# CoffretClimatiquePCBV3.net
KiCad netlist of a schematic drawn in EAGLE
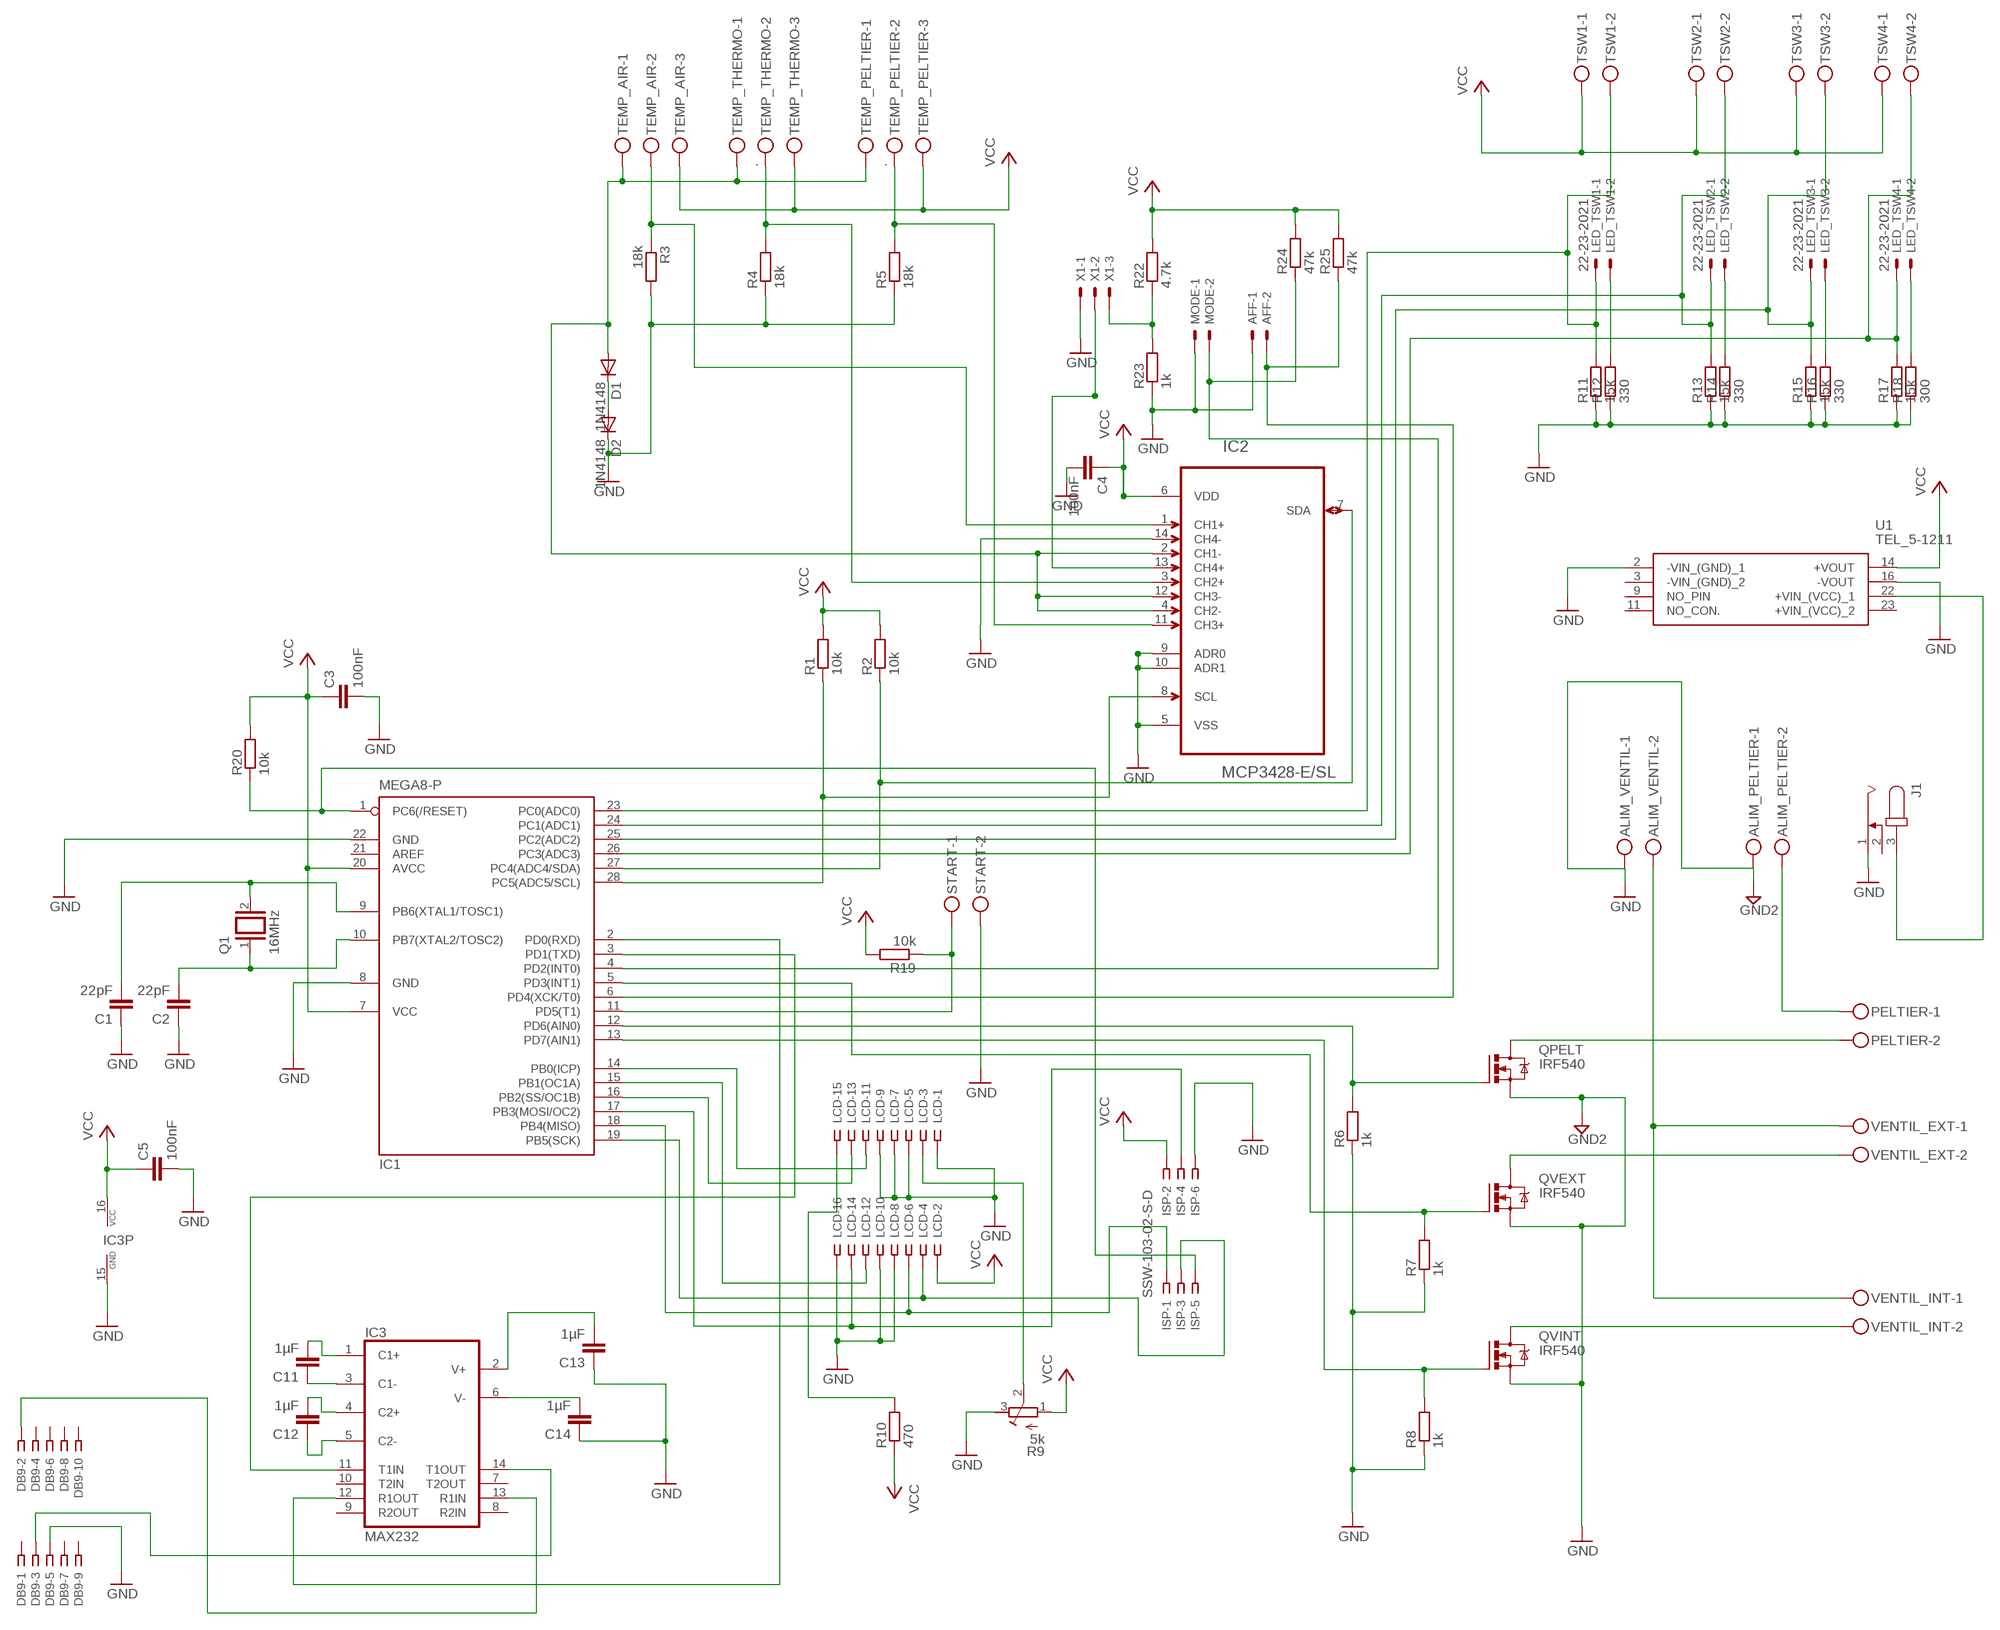
[diagram p0: schematic, sheet 1]

(export (version "E")
  (design (tool "Eeschema 10.0.6"))
  (components
    (comp (ref "AFF")
      (value "22-23-2021")
      (footprint "eagle-import:22-23-2021")
      (fields (field (name "MF") "MOLEX"))
      (libsource (lib "eagle-import") (part "22-23-2021"))
    )
    (comp (ref "ALIM_PELTIER")
      (value "MKDSN1,5/2-5,08")
      (footprint "eagle-import:MKDSN1,5_2-5,08")
      (fields (field (name "MPN") "MKDSN 1,5/2-5.08"))
      (libsource (lib "eagle-import") (part "MKDSN1,5/2-5,08"))
    )
    (comp (ref "ALIM_VENTIL")
      (value "MKDSN1,5/2-5,08")
      (footprint "eagle-import:MKDSN1,5_2-5,08")
      (fields (field (name "MPN") "MKDSN 1,5/2-5.08"))
      (libsource (lib "eagle-import") (part "MKDSN1,5/2-5,08"))
    )
    (comp (ref "C1")
      (value "22pF")
      (footprint "eagle-import:C075-032X103")
      (libsource (lib "eagle-import") (part "C-EU075-032X103"))
    )
    (comp (ref "C2")
      (value "22pF")
      (footprint "eagle-import:C075-032X103")
      (libsource (lib "eagle-import") (part "C-EU075-032X103"))
    )
    (comp (ref "C3")
      (value "100nF")
      (footprint "eagle-import:C1206")
      (libsource (lib "eagle-import") (part "C-EUC1206"))
    )
    (comp (ref "C4")
      (value "100nF")
      (footprint "eagle-import:C1206")
      (libsource (lib "eagle-import") (part "C-EUC1206"))
    )
    (comp (ref "C5")
      (value "100nF")
      (footprint "eagle-import:C1206")
      (libsource (lib "eagle-import") (part "C-EUC1206"))
    )
    (comp (ref "C11")
      (value "1µF")
      (footprint "eagle-import:C1206")
      (libsource (lib "eagle-import") (part "C-EUC1206"))
    )
    (comp (ref "C12")
      (value "1µF")
      (footprint "eagle-import:C1206")
      (libsource (lib "eagle-import") (part "C-EUC1206"))
    )
    (comp (ref "C13")
      (value "1µF")
      (footprint "eagle-import:C1206")
      (libsource (lib "eagle-import") (part "C-EUC1206"))
    )
    (comp (ref "C14")
      (value "1µF")
      (footprint "eagle-import:C1206")
      (libsource (lib "eagle-import") (part "C-EUC1206"))
    )
    (comp (ref "D1")
      (value "1N4148")
      (footprint "eagle-import:DO35-10")
      (libsource (lib "eagle-import") (part "1N4148DO35-10"))
    )
    (comp (ref "D2")
      (value "1N4148")
      (footprint "eagle-import:DO35-10")
      (libsource (lib "eagle-import") (part "1N4148DO35-10"))
    )
    (comp (ref "DB9")
      (value "SSW-105-02-S-D")
      (footprint "eagle-import:SSW-105-02-S-D")
      (libsource (lib "eagle-import") (part "SSW-105-02-S-D"))
    )
    (comp (ref "IC1")
      (value "MEGA8-P")
      (footprint "eagle-import:DIL28-3")
      (libsource (lib "eagle-import") (part "MEGA8-P"))
    )
    (comp (ref "IC2")
      (value "MCP3428-E/SL")
      (footprint "eagle-import:SOIC127P600X175-14N")
      (libsource (lib "eagle-import") (part "MCP3428-E/SL"))
    )
    (comp (ref "IC3")
      (value "MAX232")
      (footprint "eagle-import:DIL16")
      (fields (field (name "MF") "MAXIM") (field (name "MPN") "MAX232ACPE+"))
      (libsource (lib "eagle-import") (part "MAX232"))
    )
    (comp (ref "ISP")
      (value "SSW-103-02-S-D")
      (footprint "eagle-import:SSW-103-02-S-D")
      (libsource (lib "eagle-import") (part "SSW-103-02-S-D"))
    )
    (comp (ref "J1")
      (value "JACK-PLUG1")
      (footprint "eagle-import:SPC4078")
      (libsource (lib "eagle-import") (part "JACK-PLUG1"))
    )
    (comp (ref "LCD")
      (value "SSW-108-02-S-D")
      (footprint "eagle-import:SSW-108-02-S-D")
      (libsource (lib "eagle-import") (part "SSW-108-02-S-D"))
    )
    (comp (ref "LED_TSW1")
      (value "22-23-2021")
      (footprint "eagle-import:22-23-2021")
      (fields (field (name "MF") "MOLEX"))
      (libsource (lib "eagle-import") (part "22-23-2021"))
    )
    (comp (ref "LED_TSW2")
      (value "22-23-2021")
      (footprint "eagle-import:22-23-2021")
      (fields (field (name "MF") "MOLEX"))
      (libsource (lib "eagle-import") (part "22-23-2021"))
    )
    (comp (ref "LED_TSW3")
      (value "22-23-2021")
      (footprint "eagle-import:22-23-2021")
      (fields (field (name "MF") "MOLEX"))
      (libsource (lib "eagle-import") (part "22-23-2021"))
    )
    (comp (ref "LED_TSW4")
      (value "22-23-2021")
      (footprint "eagle-import:22-23-2021")
      (fields (field (name "MF") "MOLEX"))
      (libsource (lib "eagle-import") (part "22-23-2021"))
    )
    (comp (ref "MODE")
      (value "22-23-2021")
      (footprint "eagle-import:22-23-2021")
      (fields (field (name "MF") "MOLEX"))
      (libsource (lib "eagle-import") (part "22-23-2021"))
    )
    (comp (ref "PELTIER")
      (value "MKDSN1,5/2-5,08")
      (footprint "eagle-import:MKDSN1,5_2-5,08")
      (fields (field (name "MPN") "MKDSN 1,5/2-5.08"))
      (libsource (lib "eagle-import") (part "MKDSN1,5/2-5,08"))
    )
    (comp (ref "Q1")
      (value "16MHz")
      (footprint "eagle-import:QS")
      (libsource (lib "eagle-import") (part "XTAL/S"))
    )
    (comp (ref "QPELT")
      (value "IRF540")
      (footprint "eagle-import:TO220BV")
      (libsource (lib "eagle-import") (part "IRF540"))
    )
    (comp (ref "QVEXT")
      (value "IRF540")
      (footprint "eagle-import:TO220BV")
      (libsource (lib "eagle-import") (part "IRF540"))
    )
    (comp (ref "QVINT")
      (value "IRF540")
      (footprint "eagle-import:TO220BV")
      (libsource (lib "eagle-import") (part "IRF540"))
    )
    (comp (ref "R1")
      (value "10k")
      (footprint "eagle-import:R0805")
      (libsource (lib "eagle-import") (part "R-EU_R0805"))
    )
    (comp (ref "R2")
      (value "10k")
      (footprint "eagle-import:R0805")
      (libsource (lib "eagle-import") (part "R-EU_R0805"))
    )
    (comp (ref "R3")
      (value "18k")
      (footprint "eagle-import:0207_10")
      (libsource (lib "eagle-import") (part "R-EU_0207/10"))
    )
    (comp (ref "R4")
      (value "18k")
      (footprint "eagle-import:0207_10")
      (libsource (lib "eagle-import") (part "R-EU_0207/10"))
    )
    (comp (ref "R5")
      (value "18k")
      (footprint "eagle-import:0207_10")
      (libsource (lib "eagle-import") (part "R-EU_0207/10"))
    )
    (comp (ref "R6")
      (value "1k")
      (footprint "eagle-import:0207_10")
      (libsource (lib "eagle-import") (part "R-EU_0207/10"))
    )
    (comp (ref "R7")
      (value "1k")
      (footprint "eagle-import:0207_10")
      (libsource (lib "eagle-import") (part "R-EU_0207/10"))
    )
    (comp (ref "R8")
      (value "1k")
      (footprint "eagle-import:0207_10")
      (libsource (lib "eagle-import") (part "R-EU_0207/10"))
    )
    (comp (ref "R9")
      (value "5k")
      (footprint "eagle-import:RTRIM64P")
      (libsource (lib "eagle-import") (part "R-TRIMM64P"))
    )
    (comp (ref "R10")
      (value "470")
      (footprint "eagle-import:0207_10")
      (libsource (lib "eagle-import") (part "R-EU_0207/10"))
    )
    (comp (ref "R11")
      (value "15k")
      (footprint "eagle-import:0207_10")
      (libsource (lib "eagle-import") (part "R-EU_0207/10"))
    )
    (comp (ref "R12")
      (value "330")
      (footprint "eagle-import:0207_10")
      (libsource (lib "eagle-import") (part "R-EU_0207/10"))
    )
    (comp (ref "R13")
      (value "15k")
      (footprint "eagle-import:0207_10")
      (libsource (lib "eagle-import") (part "R-EU_0207/10"))
    )
    (comp (ref "R14")
      (value "330")
      (footprint "eagle-import:0207_10")
      (libsource (lib "eagle-import") (part "R-EU_0207/10"))
    )
    (comp (ref "R15")
      (value "15k")
      (footprint "eagle-import:0207_10")
      (libsource (lib "eagle-import") (part "R-EU_0207/10"))
    )
    (comp (ref "R16")
      (value "330")
      (footprint "eagle-import:0207_10")
      (libsource (lib "eagle-import") (part "R-EU_0207/10"))
    )
    (comp (ref "R17")
      (value "15k")
      (footprint "eagle-import:0207_10")
      (libsource (lib "eagle-import") (part "R-EU_0207/10"))
    )
    (comp (ref "R18")
      (value "300")
      (footprint "eagle-import:0207_10")
      (libsource (lib "eagle-import") (part "R-EU_0207/10"))
    )
    (comp (ref "R19")
      (value "10k")
      (footprint "eagle-import:0207_10")
      (libsource (lib "eagle-import") (part "R-EU_0207/10"))
    )
    (comp (ref "R20")
      (value "10k")
      (footprint "eagle-import:0207_10")
      (libsource (lib "eagle-import") (part "R-EU_0207/10"))
    )
    (comp (ref "R22")
      (value "4.7k")
      (footprint "eagle-import:0207_10")
      (libsource (lib "eagle-import") (part "R-EU_0207/10"))
    )
    (comp (ref "R23")
      (value "1k")
      (footprint "eagle-import:0207_10")
      (libsource (lib "eagle-import") (part "R-EU_0207/10"))
    )
    (comp (ref "R24")
      (value "47k")
      (footprint "eagle-import:0207_10")
      (libsource (lib "eagle-import") (part "R-EU_0207/10"))
    )
    (comp (ref "R25")
      (value "47k")
      (footprint "eagle-import:0207_10")
      (libsource (lib "eagle-import") (part "R-EU_0207/10"))
    )
    (comp (ref "START")
      (value "MKDSN1,5/2-5,08")
      (footprint "eagle-import:MKDSN1,5_2-5,08")
      (fields (field (name "MPN") "MKDSN 1,5/2-5.08"))
      (libsource (lib "eagle-import") (part "MKDSN1,5/2-5,08"))
    )
    (comp (ref "TEMP_AIR")
      (value "MKDSN1,5/3-5,08")
      (footprint "eagle-import:MKDSN1,5_3-5,08")
      (fields (field (name "MPN") "SMKDSN1,5/3-5,08"))
      (libsource (lib "eagle-import") (part "MKDSN1,5/3-5,08"))
    )
    (comp (ref "TEMP_PELTIER")
      (value ".")
      (footprint "eagle-import:MKDSN1,5_3-5,08")
      (fields (field (name "MPN") "SMKDSN1,5/3-5,08"))
      (libsource (lib "eagle-import") (part "MKDSN1,5/3-5,08"))
    )
    (comp (ref "TEMP_THERMO")
      (value ".")
      (footprint "eagle-import:MKDSN1,5_3-5,08")
      (fields (field (name "MPN") "SMKDSN1,5/3-5,08"))
      (libsource (lib "eagle-import") (part "MKDSN1,5/3-5,08"))
    )
    (comp (ref "TSW1")
      (value "MKDSN1,5/2-5,08")
      (footprint "eagle-import:MKDSN1,5_2-5,08")
      (fields (field (name "MPN") "MKDSN 1,5/2-5.08"))
      (libsource (lib "eagle-import") (part "MKDSN1,5/2-5,08"))
    )
    (comp (ref "TSW2")
      (value "MKDSN1,5/2-5,08")
      (footprint "eagle-import:MKDSN1,5_2-5,08")
      (fields (field (name "MPN") "MKDSN 1,5/2-5.08"))
      (libsource (lib "eagle-import") (part "MKDSN1,5/2-5,08"))
    )
    (comp (ref "TSW3")
      (value "MKDSN1,5/2-5,08")
      (footprint "eagle-import:MKDSN1,5_2-5,08")
      (fields (field (name "MPN") "MKDSN 1,5/2-5.08"))
      (libsource (lib "eagle-import") (part "MKDSN1,5/2-5,08"))
    )
    (comp (ref "TSW4")
      (value "MKDSN1,5/2-5,08")
      (footprint "eagle-import:MKDSN1,5_2-5,08")
      (fields (field (name "MPN") "MKDSN 1,5/2-5.08"))
      (libsource (lib "eagle-import") (part "MKDSN1,5/2-5,08"))
    )
    (comp (ref "U1")
      (value "TEL_5-1211")
      (footprint "eagle-import:TEL-5-1211")
      (fields
        (field (name "MANUFACTURER_PART_NUMBER") "TEL 5-1211")
        (field (name "MOUSER_PART_NUMBER") "495-TEL-5-1211")
        (field (name "RS_PART_NUMBER") "4667051")
      )
      (libsource (lib "eagle-import") (part "TEL_5-1211"))
    )
    (comp (ref "VENTIL_EXT")
      (value "MKDSN1,5/2-5,08")
      (footprint "eagle-import:MKDSN1,5_2-5,08")
      (fields (field (name "MPN") "MKDSN 1,5/2-5.08"))
      (libsource (lib "eagle-import") (part "MKDSN1,5/2-5,08"))
    )
    (comp (ref "VENTIL_INT")
      (value "MKDSN1,5/2-5,08")
      (footprint "eagle-import:MKDSN1,5_2-5,08")
      (fields (field (name "MPN") "MKDSN 1,5/2-5.08"))
      (libsource (lib "eagle-import") (part "MKDSN1,5/2-5,08"))
    )
    (comp (ref "X1")
      (value "22-23-2031")
      (footprint "eagle-import:22-23-2031")
      (fields (field (name "MF") "MOLEX"))
      (libsource (lib "eagle-import") (part "22-23-2031"))
    )
  )
  (nets
    (net (code "1") (name "GND") (class "Default")
      (node (ref "AFF") (pin "1") (pinfunction "S_1") (pintype "passive"))
      (node (ref "ALIM_PELTIER") (pin "1") (pinfunction "KL_1") (pintype "passive"))
      (node (ref "ALIM_VENTIL") (pin "1") (pinfunction "KL_1") (pintype "passive"))
      (node (ref "C1") (pin "1") (pinfunction "1_1") (pintype "passive"))
      (node (ref "C13") (pin "1") (pinfunction "1_1") (pintype "passive"))
      (node (ref "C14") (pin "1") (pinfunction "1_1") (pintype "passive"))
      (node (ref "C2") (pin "1") (pinfunction "1_1") (pintype "passive"))
      (node (ref "C3") (pin "2") (pinfunction "2_2") (pintype "passive"))
      (node (ref "C4") (pin "2") (pinfunction "2_2") (pintype "passive"))
      (node (ref "C5") (pin "2") (pinfunction "2_2") (pintype "passive"))
      (node (ref "D2") (pin "C") (pinfunction "C_C") (pintype "passive"))
      (node (ref "DB9") (pin "5") (pinfunction "1_5") (pintype "passive"))
      (node (ref "IC1") (pin "22") (pinfunction "GND_22") (pintype "power_in"))
      (node (ref "IC1") (pin "8") (pinfunction "GND_8") (pintype "power_in"))
      (node (ref "IC2") (pin "10") (pinfunction "ADR1_10") (pintype "passive"))
      (node (ref "IC2") (pin "14") (pinfunction "CH4-_14") (pintype "input"))
      (node (ref "IC2") (pin "5") (pinfunction "VSS_5") (pintype "power_in"))
      (node (ref "IC2") (pin "9") (pinfunction "ADR0_9") (pintype "passive"))
      (node (ref "IC3") (pin "15") (pinfunction "GND_15") (pintype "power_in"))
      (node (ref "ISP") (pin "6") (pinfunction "1_6") (pintype "passive"))
      (node (ref "J1") (pin "1") (pinfunction "1_1") (pintype "passive"))
      (node (ref "LCD") (pin "1") (pinfunction "1_1") (pintype "passive"))
      (node (ref "LCD") (pin "10") (pinfunction "1_10") (pintype "passive"))
      (node (ref "LCD") (pin "16") (pinfunction "1_16") (pintype "passive"))
      (node (ref "LCD") (pin "5") (pinfunction "1_5") (pintype "passive"))
      (node (ref "LCD") (pin "7") (pinfunction "1_7") (pintype "passive"))
      (node (ref "LCD") (pin "8") (pinfunction "1_8") (pintype "passive"))
      (node (ref "LCD") (pin "9") (pinfunction "1_9") (pintype "passive"))
      (node (ref "MODE") (pin "1") (pinfunction "S_1") (pintype "passive"))
      (node (ref "QPELT") (pin "S") (pinfunction "S_S") (pintype "passive"))
      (node (ref "QVEXT") (pin "S") (pinfunction "S_S") (pintype "passive"))
      (node (ref "QVINT") (pin "S") (pinfunction "S_S") (pintype "passive"))
      (node (ref "R11") (pin "1") (pinfunction "1_1") (pintype "passive"))
      (node (ref "R12") (pin "1") (pinfunction "1_1") (pintype "passive"))
      (node (ref "R13") (pin "1") (pinfunction "1_1") (pintype "passive"))
      (node (ref "R14") (pin "1") (pinfunction "1_1") (pintype "passive"))
      (node (ref "R15") (pin "1") (pinfunction "1_1") (pintype "passive"))
      (node (ref "R16") (pin "1") (pinfunction "1_1") (pintype "passive"))
      (node (ref "R17") (pin "1") (pinfunction "1_1") (pintype "passive"))
      (node (ref "R18") (pin "1") (pinfunction "1_1") (pintype "passive"))
      (node (ref "R23") (pin "1") (pinfunction "1_1") (pintype "passive"))
      (node (ref "R3") (pin "2") (pinfunction "2_2") (pintype "passive"))
      (node (ref "R4") (pin "1") (pinfunction "1_1") (pintype "passive"))
      (node (ref "R5") (pin "1") (pinfunction "1_1") (pintype "passive"))
      (node (ref "R6") (pin "1") (pinfunction "1_1") (pintype "passive"))
      (node (ref "R7") (pin "1") (pinfunction "1_1") (pintype "passive"))
      (node (ref "R8") (pin "1") (pinfunction "1_1") (pintype "passive"))
      (node (ref "R9") (pin "3") (pinfunction "E_3") (pintype "passive"))
      (node (ref "START") (pin "2") (pinfunction "KL_2") (pintype "passive"))
      (node (ref "U1") (pin "16") (pinfunction "-VOUT_16") (pintype "bidirectional"))
      (node (ref "U1") (pin "2") (pinfunction "-VIN_(GND)_1_2") (pintype "bidirectional"))
      (node (ref "X1") (pin "1") (pinfunction "S_1") (pintype "passive"))
    )
    (net (code "2") (name "Net-(AFFB-S)") (class "Default")
      (node (ref "AFF") (pin "2") (pinfunction "S_2") (pintype "passive"))
      (node (ref "IC1") (pin "6") (pinfunction "PD4(XCK/T0)_6") (pintype "bidirectional"))
      (node (ref "R25") (pin "1") (pinfunction "1_1") (pintype "passive"))
    )
    (net (code "3") (name "Net-(ALIM_PELTIERB-KL)") (class "Default")
      (node (ref "ALIM_PELTIER") (pin "2") (pinfunction "KL_2") (pintype "passive"))
      (node (ref "PELTIER") (pin "1") (pinfunction "KL_1") (pintype "passive"))
    )
    (net (code "4") (name "Net-(ALIM_VENTILB-KL)") (class "Default")
      (node (ref "ALIM_VENTIL") (pin "2") (pinfunction "KL_2") (pintype "passive"))
      (node (ref "VENTIL_EXT") (pin "1") (pinfunction "KL_1") (pintype "passive"))
      (node (ref "VENTIL_INT") (pin "1") (pinfunction "KL_1") (pintype "passive"))
    )
    (net (code "5") (name "Net-(D1-PadC)") (class "Default")
      (node (ref "D1") (pin "C") (pinfunction "C_C") (pintype "passive"))
      (node (ref "D2") (pin "A") (pinfunction "A_A") (pintype "passive"))
    )
    (net (code "6") (name "Net-(DB9C-1)") (class "Default")
      (node (ref "DB9") (pin "2") (pinfunction "1_2") (pintype "passive"))
      (node (ref "IC3") (pin "13") (pinfunction "R1IN_13") (pintype "input"))
    )
    (net (code "7") (name "Net-(DB9D-1)") (class "Default")
      (node (ref "DB9") (pin "3") (pinfunction "1_3") (pintype "passive"))
      (node (ref "IC3") (pin "14") (pinfunction "T1OUT_14") (pintype "output"))
    )
    (net (code "8") (name "Net-(IC1-PB0(ICP))") (class "Default")
      (node (ref "IC1") (pin "14") (pinfunction "PB0(ICP)_14") (pintype "bidirectional"))
      (node (ref "LCD") (pin "11") (pinfunction "1_11") (pintype "passive"))
    )
    (net (code "9") (name "Net-(IC1-PB1(OC1A))") (class "Default")
      (node (ref "IC1") (pin "15") (pinfunction "PB1(OC1A)_15") (pintype "bidirectional"))
      (node (ref "LCD") (pin "12") (pinfunction "1_12") (pintype "passive"))
    )
    (net (code "10") (name "Net-(IC1-PB2(SS{slash}OC1B))") (class "Default")
      (node (ref "IC1") (pin "16") (pinfunction "PB2(SS/OC1B)_16") (pintype "bidirectional"))
      (node (ref "LCD") (pin "13") (pinfunction "1_13") (pintype "passive"))
    )
    (net (code "11") (name "Net-(IC1-PB3(MOSI{slash}OC2))") (class "Default")
      (node (ref "IC1") (pin "17") (pinfunction "PB3(MOSI/OC2)_17") (pintype "bidirectional"))
      (node (ref "ISP") (pin "4") (pinfunction "1_4") (pintype "passive"))
      (node (ref "LCD") (pin "14") (pinfunction "1_14") (pintype "passive"))
    )
    (net (code "12") (name "Net-(IC1-PB4(MISO))") (class "Default")
      (node (ref "IC1") (pin "18") (pinfunction "PB4(MISO)_18") (pintype "bidirectional"))
      (node (ref "ISP") (pin "1") (pinfunction "1_1") (pintype "passive"))
      (node (ref "LCD") (pin "6") (pinfunction "1_6") (pintype "passive"))
    )
    (net (code "13") (name "Net-(IC1-PB5(SCK))") (class "Default")
      (node (ref "IC1") (pin "19") (pinfunction "PB5(SCK)_19") (pintype "bidirectional"))
      (node (ref "ISP") (pin "3") (pinfunction "1_3") (pintype "passive"))
      (node (ref "LCD") (pin "4") (pinfunction "1_4") (pintype "passive"))
    )
    (net (code "14") (name "Net-(IC1-PB6(XTAL1{slash}TOSC1))") (class "Default")
      (node (ref "C1") (pin "2") (pinfunction "2_2") (pintype "passive"))
      (node (ref "IC1") (pin "9") (pinfunction "PB6(XTAL1/TOSC1)_9") (pintype "bidirectional"))
      (node (ref "Q1") (pin "2") (pinfunction "2_2") (pintype "passive"))
    )
    (net (code "15") (name "Net-(IC1-PB7(XTAL2{slash}TOSC2))") (class "Default")
      (node (ref "C2") (pin "2") (pinfunction "2_2") (pintype "passive"))
      (node (ref "IC1") (pin "10") (pinfunction "PB7(XTAL2/TOSC2)_10") (pintype "bidirectional"))
      (node (ref "Q1") (pin "1") (pinfunction "1_1") (pintype "passive"))
    )
    (net (code "16") (name "Net-(IC1-PC0(ADC0))") (class "Default")
      (node (ref "IC1") (pin "23") (pinfunction "PC0(ADC0)_23") (pintype "bidirectional"))
      (node (ref "LED_TSW1") (pin "1") (pinfunction "S_1") (pintype "passive"))
      (node (ref "R11") (pin "2") (pinfunction "2_2") (pintype "passive"))
      (node (ref "TSW1") (pin "2") (pinfunction "KL_2") (pintype "passive"))
    )
    (net (code "17") (name "Net-(IC1-PC1(ADC1))") (class "Default")
      (node (ref "IC1") (pin "24") (pinfunction "PC1(ADC1)_24") (pintype "bidirectional"))
      (node (ref "LED_TSW2") (pin "1") (pinfunction "S_1") (pintype "passive"))
      (node (ref "R13") (pin "2") (pinfunction "2_2") (pintype "passive"))
      (node (ref "TSW2") (pin "2") (pinfunction "KL_2") (pintype "passive"))
    )
    (net (code "18") (name "Net-(IC1-PC2(ADC2))") (class "Default")
      (node (ref "IC1") (pin "25") (pinfunction "PC2(ADC2)_25") (pintype "bidirectional"))
      (node (ref "LED_TSW3") (pin "1") (pinfunction "S_1") (pintype "passive"))
      (node (ref "R15") (pin "2") (pinfunction "2_2") (pintype "passive"))
      (node (ref "TSW3") (pin "2") (pinfunction "KL_2") (pintype "passive"))
    )
    (net (code "19") (name "Net-(IC1-PC3(ADC3))") (class "Default")
      (node (ref "IC1") (pin "26") (pinfunction "PC3(ADC3)_26") (pintype "bidirectional"))
      (node (ref "LED_TSW4") (pin "1") (pinfunction "S_1") (pintype "passive"))
      (node (ref "R17") (pin "2") (pinfunction "2_2") (pintype "passive"))
      (node (ref "TSW4") (pin "2") (pinfunction "KL_2") (pintype "passive"))
    )
    (net (code "20") (name "Net-(IC1-PC4(ADC4{slash}SDA))") (class "Default")
      (node (ref "IC1") (pin "27") (pinfunction "PC4(ADC4/SDA)_27") (pintype "bidirectional"))
      (node (ref "IC2") (pin "7") (pinfunction "SDA_7") (pintype "bidirectional"))
      (node (ref "R2") (pin "1") (pinfunction "1_1") (pintype "passive"))
    )
    (net (code "21") (name "Net-(IC1-PC5(ADC5{slash}SCL))") (class "Default")
      (node (ref "IC1") (pin "28") (pinfunction "PC5(ADC5/SCL)_28") (pintype "bidirectional"))
      (node (ref "IC2") (pin "8") (pinfunction "SCL_8") (pintype "input"))
      (node (ref "R1") (pin "1") (pinfunction "1_1") (pintype "passive"))
    )
    (net (code "22") (name "Net-(IC1-PC6({slash}RESET))") (class "Default")
      (node (ref "IC1") (pin "1") (pinfunction "PC6(/RESET)_1") (pintype "bidirectional"))
      (node (ref "ISP") (pin "5") (pinfunction "1_5") (pintype "passive"))
      (node (ref "R20") (pin "1") (pinfunction "1_1") (pintype "passive"))
    )
    (net (code "23") (name "Net-(IC1-PD0(RXD))") (class "Default")
      (node (ref "IC1") (pin "2") (pinfunction "PD0(RXD)_2") (pintype "bidirectional"))
      (node (ref "IC3") (pin "12") (pinfunction "R1OUT_12") (pintype "output"))
    )
    (net (code "24") (name "Net-(IC1-PD1(TXD))") (class "Default")
      (node (ref "IC1") (pin "3") (pinfunction "PD1(TXD)_3") (pintype "bidirectional"))
      (node (ref "IC3") (pin "11") (pinfunction "T1IN_11") (pintype "input"))
    )
    (net (code "25") (name "Net-(IC1-PD2(INT0))") (class "Default")
      (node (ref "IC1") (pin "4") (pinfunction "PD2(INT0)_4") (pintype "bidirectional"))
      (node (ref "MODE") (pin "2") (pinfunction "S_2") (pintype "passive"))
      (node (ref "R24") (pin "1") (pinfunction "1_1") (pintype "passive"))
    )
    (net (code "26") (name "Net-(IC1-PD3(INT1))") (class "Default")
      (node (ref "IC1") (pin "5") (pinfunction "PD3(INT1)_5") (pintype "bidirectional"))
      (node (ref "QVEXT") (pin "G") (pinfunction "G_G") (pintype "passive"))
      (node (ref "R7") (pin "2") (pinfunction "2_2") (pintype "passive"))
    )
    (net (code "27") (name "Net-(IC1-PD5(T1))") (class "Default")
      (node (ref "IC1") (pin "11") (pinfunction "PD5(T1)_11") (pintype "bidirectional"))
      (node (ref "R19") (pin "1") (pinfunction "1_1") (pintype "passive"))
      (node (ref "START") (pin "1") (pinfunction "KL_1") (pintype "passive"))
    )
    (net (code "28") (name "Net-(IC1-PD6(AIN0))") (class "Default")
      (node (ref "IC1") (pin "12") (pinfunction "PD6(AIN0)_12") (pintype "bidirectional"))
      (node (ref "QPELT") (pin "G") (pinfunction "G_G") (pintype "passive"))
      (node (ref "R6") (pin "2") (pinfunction "2_2") (pintype "passive"))
    )
    (net (code "29") (name "Net-(IC1-PD7(AIN1))") (class "Default")
      (node (ref "IC1") (pin "13") (pinfunction "PD7(AIN1)_13") (pintype "bidirectional"))
      (node (ref "QVINT") (pin "G") (pinfunction "G_G") (pintype "passive"))
      (node (ref "R8") (pin "2") (pinfunction "2_2") (pintype "passive"))
    )
    (net (code "30") (name "Net-(IC2-CH1+)") (class "Default")
      (node (ref "IC2") (pin "1") (pinfunction "CH1+_1") (pintype "input"))
      (node (ref "R3") (pin "1") (pinfunction "1_1") (pintype "passive"))
      (node (ref "TEMP_AIR") (pin "2") (pinfunction "KL_2") (pintype "passive"))
    )
    (net (code "31") (name "Net-(IC2-CH1-)") (class "Default")
      (node (ref "D1") (pin "A") (pinfunction "A_A") (pintype "passive"))
      (node (ref "IC2") (pin "12") (pinfunction "CH3-_12") (pintype "input"))
      (node (ref "IC2") (pin "2") (pinfunction "CH1-_2") (pintype "input"))
      (node (ref "IC2") (pin "4") (pinfunction "CH2-_4") (pintype "input"))
      (node (ref "TEMP_AIR") (pin "1") (pinfunction "KL_1") (pintype "passive"))
      (node (ref "TEMP_PELTIER") (pin "1") (pinfunction "KL_1") (pintype "passive"))
      (node (ref "TEMP_THERMO") (pin "1") (pinfunction "KL_1") (pintype "passive"))
    )
    (net (code "32") (name "Net-(IC2-CH2+)") (class "Default")
      (node (ref "IC2") (pin "3") (pinfunction "CH2+_3") (pintype "input"))
      (node (ref "R4") (pin "2") (pinfunction "2_2") (pintype "passive"))
      (node (ref "TEMP_THERMO") (pin "2") (pinfunction "KL_2") (pintype "passive"))
    )
    (net (code "33") (name "Net-(IC2-CH3+)") (class "Default")
      (node (ref "IC2") (pin "11") (pinfunction "CH3+_11") (pintype "input"))
      (node (ref "R5") (pin "2") (pinfunction "2_2") (pintype "passive"))
      (node (ref "TEMP_PELTIER") (pin "2") (pinfunction "KL_2") (pintype "passive"))
    )
    (net (code "34") (name "Net-(IC2-CH4+)") (class "Default")
      (node (ref "IC2") (pin "13") (pinfunction "CH4+_13") (pintype "input"))
      (node (ref "X1") (pin "2") (pinfunction "S_2") (pintype "passive"))
    )
    (net (code "35") (name "Net-(IC3A-C1+)") (class "Default")
      (node (ref "C11") (pin "2") (pinfunction "2_2") (pintype "passive"))
      (node (ref "IC3") (pin "1") (pinfunction "C1+_1") (pintype "bidirectional"))
    )
    (net (code "36") (name "Net-(IC3A-C1-)") (class "Default")
      (node (ref "C11") (pin "1") (pinfunction "1_1") (pintype "passive"))
      (node (ref "IC3") (pin "3") (pinfunction "C1-_3") (pintype "bidirectional"))
    )
    (net (code "37") (name "Net-(IC3A-C2+)") (class "Default")
      (node (ref "C12") (pin "2") (pinfunction "2_2") (pintype "passive"))
      (node (ref "IC3") (pin "4") (pinfunction "C2+_4") (pintype "bidirectional"))
    )
    (net (code "38") (name "Net-(IC3A-C2-)") (class "Default")
      (node (ref "C12") (pin "1") (pinfunction "1_1") (pintype "passive"))
      (node (ref "IC3") (pin "5") (pinfunction "C2-_5") (pintype "bidirectional"))
    )
    (net (code "39") (name "Net-(IC3A-V+)") (class "Default")
      (node (ref "C13") (pin "2") (pinfunction "2_2") (pintype "passive"))
      (node (ref "IC3") (pin "2") (pinfunction "V+_2") (pintype "bidirectional"))
    )
    (net (code "40") (name "Net-(IC3A-V-)") (class "Default")
      (node (ref "C14") (pin "2") (pinfunction "2_2") (pintype "passive"))
      (node (ref "IC3") (pin "6") (pinfunction "V-_6") (pintype "bidirectional"))
    )
    (net (code "41") (name "Net-(LCDG-1)") (class "Default")
      (node (ref "LCD") (pin "15") (pinfunction "1_15") (pintype "passive"))
      (node (ref "R10") (pin "2") (pinfunction "2_2") (pintype "passive"))
    )
    (net (code "42") (name "Net-(LCDJ-1)") (class "Default")
      (node (ref "LCD") (pin "3") (pinfunction "1_3") (pintype "passive"))
      (node (ref "R9") (pin "2") (pinfunction "S_2") (pintype "passive"))
    )
    (net (code "43") (name "Net-(LED_TSW1B-S)") (class "Default")
      (node (ref "LED_TSW1") (pin "2") (pinfunction "S_2") (pintype "passive"))
      (node (ref "R12") (pin "2") (pinfunction "2_2") (pintype "passive"))
    )
    (net (code "44") (name "Net-(LED_TSW2B-S)") (class "Default")
      (node (ref "LED_TSW2") (pin "2") (pinfunction "S_2") (pintype "passive"))
      (node (ref "R14") (pin "2") (pinfunction "2_2") (pintype "passive"))
    )
    (net (code "45") (name "Net-(LED_TSW3B-S)") (class "Default")
      (node (ref "LED_TSW3") (pin "2") (pinfunction "S_2") (pintype "passive"))
      (node (ref "R16") (pin "2") (pinfunction "2_2") (pintype "passive"))
    )
    (net (code "46") (name "Net-(LED_TSW4B-S)") (class "Default")
      (node (ref "LED_TSW4") (pin "2") (pinfunction "S_2") (pintype "passive"))
      (node (ref "R18") (pin "2") (pinfunction "2_2") (pintype "passive"))
    )
    (net (code "47") (name "Net-(PELTIERB-KL)") (class "Default")
      (node (ref "PELTIER") (pin "2") (pinfunction "KL_2") (pintype "passive"))
      (node (ref "QPELT") (pin "D") (pinfunction "D_D") (pintype "passive"))
    )
    (net (code "48") (name "Net-(U1-+VIN_(VCC)_1)") (class "Default")
      (node (ref "J1") (pin "3") (pinfunction "3_3") (pintype "passive"))
      (node (ref "U1") (pin "22") (pinfunction "+VIN_(VCC)_1_22") (pintype "bidirectional"))
    )
    (net (code "49") (name "Net-(VENTIL_EXTB-KL)") (class "Default")
      (node (ref "QVEXT") (pin "D") (pinfunction "D_D") (pintype "passive"))
      (node (ref "VENTIL_EXT") (pin "2") (pinfunction "KL_2") (pintype "passive"))
    )
    (net (code "50") (name "Net-(VENTIL_INTB-KL)") (class "Default")
      (node (ref "QVINT") (pin "D") (pinfunction "D_D") (pintype "passive"))
      (node (ref "VENTIL_INT") (pin "2") (pinfunction "KL_2") (pintype "passive"))
    )
    (net (code "51") (name "Net-(X1C-S)") (class "Default")
      (node (ref "R22") (pin "1") (pinfunction "1_1") (pintype "passive"))
      (node (ref "R23") (pin "2") (pinfunction "2_2") (pintype "passive"))
      (node (ref "X1") (pin "3") (pinfunction "S_3") (pintype "passive"))
    )
    (net (code "52") (name "VCC") (class "Default")
      (node (ref "C3") (pin "1") (pinfunction "1_1") (pintype "passive"))
      (node (ref "C4") (pin "1") (pinfunction "1_1") (pintype "passive"))
      (node (ref "C5") (pin "1") (pinfunction "1_1") (pintype "passive"))
      (node (ref "IC1") (pin "20") (pinfunction "AVCC_20") (pintype "power_in"))
      (node (ref "IC1") (pin "7") (pinfunction "VCC_7") (pintype "power_in"))
      (node (ref "IC2") (pin "6") (pinfunction "VDD_6") (pintype "power_in"))
      (node (ref "IC3") (pin "16") (pinfunction "VCC_16") (pintype "power_in"))
      (node (ref "ISP") (pin "2") (pinfunction "1_2") (pintype "passive"))
      (node (ref "LCD") (pin "2") (pinfunction "1_2") (pintype "passive"))
      (node (ref "R1") (pin "2") (pinfunction "2_2") (pintype "passive"))
      (node (ref "R10") (pin "1") (pinfunction "1_1") (pintype "passive"))
      (node (ref "R19") (pin "2") (pinfunction "2_2") (pintype "passive"))
      (node (ref "R2") (pin "2") (pinfunction "2_2") (pintype "passive"))
      (node (ref "R20") (pin "2") (pinfunction "2_2") (pintype "passive"))
      (node (ref "R22") (pin "2") (pinfunction "2_2") (pintype "passive"))
      (node (ref "R24") (pin "2") (pinfunction "2_2") (pintype "passive"))
      (node (ref "R25") (pin "2") (pinfunction "2_2") (pintype "passive"))
      (node (ref "R9") (pin "1") (pinfunction "A_1") (pintype "passive"))
      (node (ref "TEMP_AIR") (pin "3") (pinfunction "KL_3") (pintype "passive"))
      (node (ref "TEMP_PELTIER") (pin "3") (pinfunction "KL_3") (pintype "passive"))
      (node (ref "TEMP_THERMO") (pin "3") (pinfunction "KL_3") (pintype "passive"))
      (node (ref "TSW1") (pin "1") (pinfunction "KL_1") (pintype "passive"))
      (node (ref "TSW2") (pin "1") (pinfunction "KL_1") (pintype "passive"))
      (node (ref "TSW3") (pin "1") (pinfunction "KL_1") (pintype "passive"))
      (node (ref "TSW4") (pin "1") (pinfunction "KL_1") (pintype "passive"))
      (node (ref "U1") (pin "14") (pinfunction "+VOUT_14") (pintype "bidirectional"))
    )
    (net (code "53") (name "unconnected-(DB9-Pad1)") (class "Default")
      (node (ref "DB9") (pin "1") (pinfunction "1_1") (pintype "passive"))
    )
    (net (code "54") (name "unconnected-(DB9B-1-Pad10)") (class "Default")
      (node (ref "DB9") (pin "10") (pinfunction "1_10") (pintype "passive"))
    )
    (net (code "55") (name "unconnected-(DB9E-1-Pad4)") (class "Default")
      (node (ref "DB9") (pin "4") (pinfunction "1_4") (pintype "passive"))
    )
    (net (code "56") (name "unconnected-(DB9G-1-Pad6)") (class "Default")
      (node (ref "DB9") (pin "6") (pinfunction "1_6") (pintype "passive"))
    )
    (net (code "57") (name "unconnected-(DB9H-1-Pad7)") (class "Default")
      (node (ref "DB9") (pin "7") (pinfunction "1_7") (pintype "passive"))
    )
    (net (code "58") (name "unconnected-(DB9I-1-Pad8)") (class "Default")
      (node (ref "DB9") (pin "8") (pinfunction "1_8") (pintype "passive"))
    )
    (net (code "59") (name "unconnected-(DB9J-1-Pad9)") (class "Default")
      (node (ref "DB9") (pin "9") (pinfunction "1_9") (pintype "passive"))
    )
    (net (code "60") (name "unconnected-(IC1-AREF-Pad21)") (class "Default")
      (node (ref "IC1") (pin "21") (pinfunction "AREF_21") (pintype "passive"))
    )
    (net (code "61") (name "unconnected-(IC3A-R2IN-Pad8)") (class "Default")
      (node (ref "IC3") (pin "8") (pinfunction "R2IN_8") (pintype "input"))
    )
    (net (code "62") (name "unconnected-(IC3A-R2OUT-Pad9)") (class "Default")
      (node (ref "IC3") (pin "9") (pinfunction "R2OUT_9") (pintype "output"))
    )
    (net (code "63") (name "unconnected-(IC3A-T2IN-Pad10)") (class "Default")
      (node (ref "IC3") (pin "10") (pinfunction "T2IN_10") (pintype "input"))
    )
    (net (code "64") (name "unconnected-(IC3A-T2OUT-Pad7)") (class "Default")
      (node (ref "IC3") (pin "7") (pinfunction "T2OUT_7") (pintype "output"))
    )
    (net (code "65") (name "unconnected-(J1-Pad2)") (class "Default")
      (node (ref "J1") (pin "2") (pinfunction "2_2") (pintype "passive"))
    )
    (net (code "66") (name "unconnected-(U1-+VIN_(VCC)_2-Pad23)") (class "Default")
      (node (ref "U1") (pin "23") (pinfunction "+VIN_(VCC)_2_23") (pintype "bidirectional"))
    )
    (net (code "67") (name "unconnected-(U1--VIN_(GND)_2-Pad3)") (class "Default")
      (node (ref "U1") (pin "3") (pinfunction "-VIN_(GND)_2_3") (pintype "bidirectional"))
    )
    (net (code "68") (name "unconnected-(U1-NO_CON.-Pad11)") (class "Default")
      (node (ref "U1") (pin "11") (pinfunction "NO_CON._11") (pintype "bidirectional"))
    )
    (net (code "69") (name "unconnected-(U1-NO_PIN-Pad9)") (class "Default")
      (node (ref "U1") (pin "9") (pinfunction "NO_PIN_9") (pintype "bidirectional"))
    )
  )
)
